# USB___mega8.net
KiCad netlist of a schematic drawn in Altium Designer
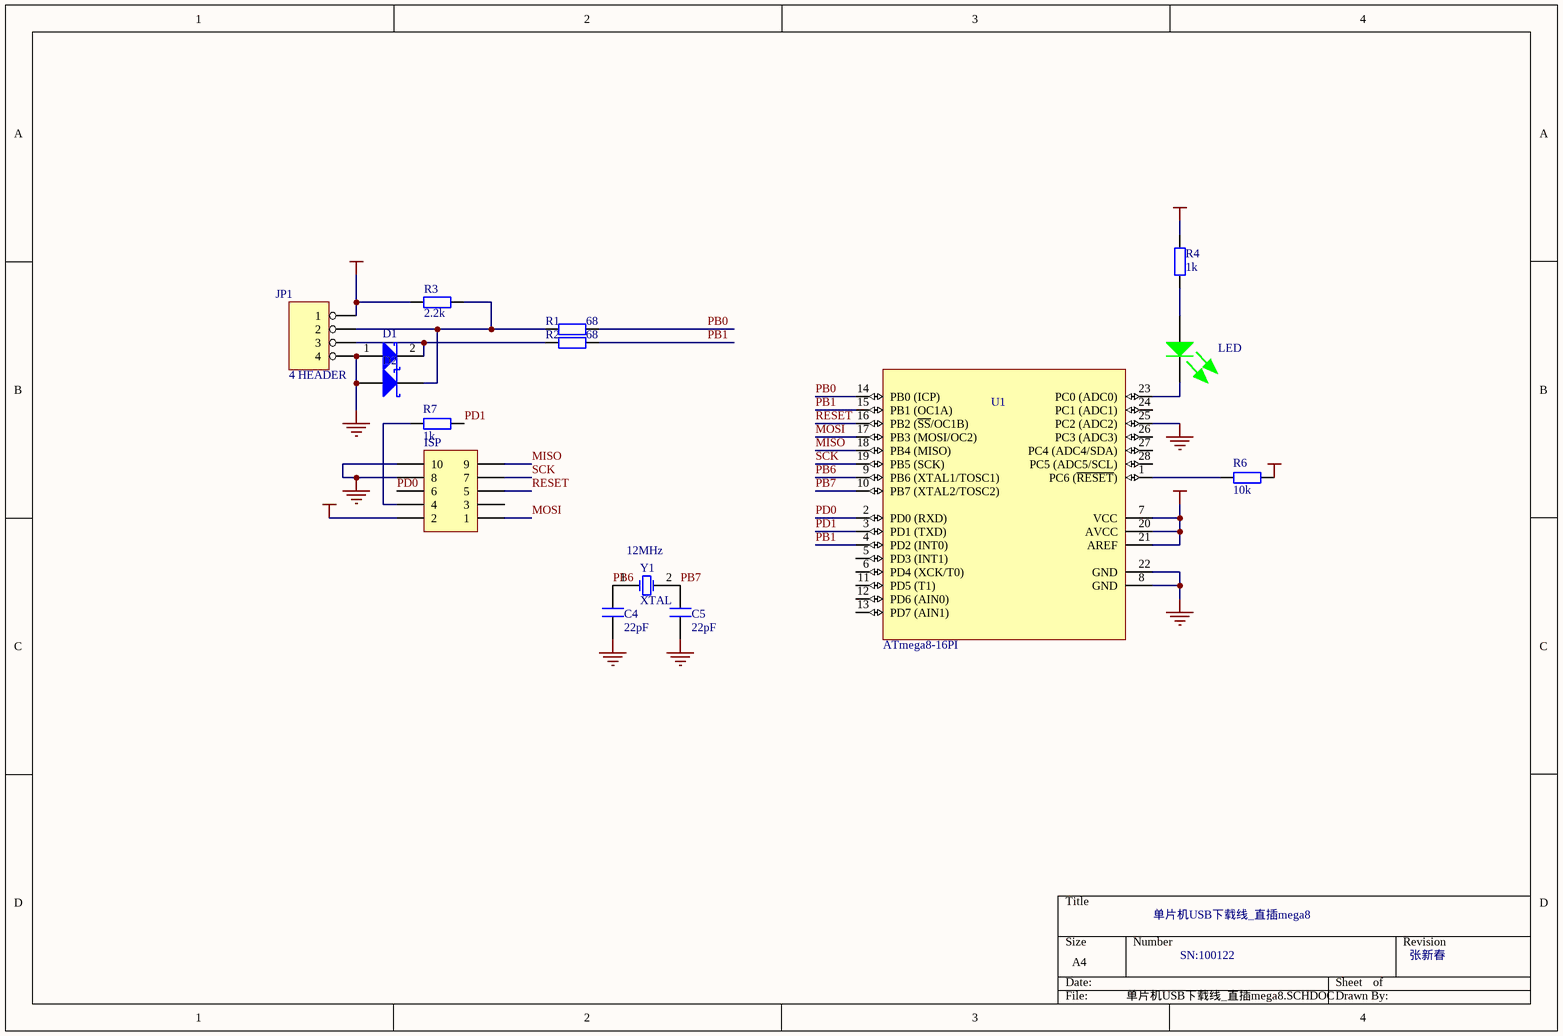
[diagram p0: 单片机USB下载线_直插mega8.SCHDOC]

(export (version "E")
  (design (tool "Eeschema 10.0.6"))
  (components
    (comp (ref "C4")
      (value "22pF")
      (footprint "TP-0805-R")
      (description "Capacitor SMD1206")
      (libsource (lib "*") (part "CAPSMD"))
    )
    (comp (ref "C5")
      (value "22pF")
      (footprint "TP-0805-R")
      (description "Capacitor SMD1206")
      (libsource (lib "*") (part "CAPSMD"))
    )
    (comp (ref "D1")
      (value "Diode 11DQ03")
      (footprint "TPDR")
      (description "Schottky Rectifier")
      (fields (field (name "PUBLISHER") "Altium Limited"))
      (libsource (lib "Miscellaneous Devices") (part "Diode 11DQ03"))
    )
    (comp (ref "D2")
      (value "Diode 11DQ03")
      (footprint "TPDR")
      (description "Schottky Rectifier")
      (fields (field (name "PUBLISHER") "Altium Limited"))
      (libsource (lib "") (part "Diode 11DQ03_1"))
    )
    (comp (ref "ISP")
      (value "~")
      (footprint "HDR2X5")
      (description "Header, 5-Pin, Dual row, Right Angle")
      (fields (field (name "MANUFACTURER") "Generic Components"))
      (libsource (lib "*") (part "MLW10A"))
    )
    (comp (ref "JP1")
      (value "4 HEADER")
      (footprint "USB-5V")
      (description "4 Pin Header")
      (libsource (lib "*") (part "4 HEADER"))
    )
    (comp (ref "LED")
      (value "~")
      (footprint "TP-0805-D")
      (description "Zöld Led 3mm")
      (libsource (lib "*") (part "LED Zöld"))
    )
    (comp (ref "R1")
      (value "68")
      (footprint "TP-0805-R")
      (description "Resistor SMD1206, 1% fémréteg")
      (libsource (lib "*") (part "RES"))
    )
    (comp (ref "R2")
      (value "68")
      (footprint "TP-0805-R")
      (description "Resistor SMD1206, 1% fémréteg")
      (libsource (lib "*") (part "RES"))
    )
    (comp (ref "R3")
      (value "2.2k")
      (footprint "TP-0805-R")
      (description "Resistor SMD1206, 1% fémréteg")
      (libsource (lib "*") (part "RES"))
    )
    (comp (ref "R4")
      (value "1k")
      (footprint "TP-0805-R")
      (description "Resistor SMD1206, 1% fémréteg")
      (libsource (lib "*") (part "RES"))
    )
    (comp (ref "R6")
      (value "10k")
      (footprint "TP-0805-R")
      (description "Resistor SMD1206, 1% fémréteg")
      (libsource (lib "*") (part "RES"))
    )
    (comp (ref "R7")
      (value "1k")
      (footprint "TP-0805-R")
      (description "Resistor SMD1206, 1% fémréteg")
      (libsource (lib "*") (part "RES"))
    )
    (comp (ref "U1")
      (value "ATmega8-16PI")
      (footprint "28P3")
      (description "8-Bit AVR Microcontroller with 8K Bytes of In-System Programmable Flash Memory")
      (fields (field (name "PUBLISHER") "Altium Limited"))
      (libsource (lib "Atmel Microcontroller 8-Bit AVR") (part "ATmega8-16PI"))
    )
    (comp (ref "Y1")
      (value "XTAL")
      (footprint "JZ_ZC")
      (description "Crystal Oscillator")
      (fields
        (field (name "MANUFACTURER") "Generic Components")
        (field (name "ALTIUM_VALUE") "12MHz")
        (field (name "PUBLISHER") "Altium Hobart Technology Centre")
      )
      (libsource (lib "*") (part "XTAL"))
    )
  )
  (nets
    (net (code "1") (name "/MISO") (class "Default")
      (node (ref "ISP") (pin "9") (pinfunction "9_9") (pintype "passive"))
      (node (ref "U1") (pin "18") (pinfunction "PB4_(MISO)_18") (pintype "bidirectional"))
    )
    (net (code "2") (name "/MOSI") (class "Default")
      (node (ref "ISP") (pin "1") (pinfunction "1_1") (pintype "passive"))
      (node (ref "U1") (pin "17") (pinfunction "PB3_(MOSI/OC2)_17") (pintype "bidirectional"))
    )
    (net (code "3") (name "/PB0") (class "Default")
      (node (ref "R1") (pin "2") (pinfunction "2_2") (pintype "passive"))
      (node (ref "U1") (pin "14") (pinfunction "PB0_(ICP)_14") (pintype "bidirectional"))
    )
    (net (code "4") (name "/PB1") (class "Default")
      (node (ref "R2") (pin "1") (pinfunction "1_1") (pintype "passive"))
      (node (ref "U1") (pin "15") (pinfunction "PB1_(OC1A)_15") (pintype "bidirectional"))
      (node (ref "U1") (pin "4") (pinfunction "PD2_(INT0)_4") (pintype "bidirectional"))
    )
    (net (code "5") (name "/PB6") (class "Default")
      (node (ref "C4") (pin "2") (pinfunction "2_2") (pintype "passive"))
      (node (ref "U1") (pin "9") (pinfunction "PB6_(XTAL1/TOSC1)_9") (pintype "bidirectional"))
      (node (ref "Y1") (pin "1") (pinfunction "OSC1_1") (pintype "passive"))
    )
    (net (code "6") (name "/PB7") (class "Default")
      (node (ref "C5") (pin "2") (pinfunction "2_2") (pintype "passive"))
      (node (ref "U1") (pin "10") (pinfunction "PB7_(XTAL2/TOSC2)_10") (pintype "bidirectional"))
      (node (ref "Y1") (pin "2") (pinfunction "OSC2_2") (pintype "passive"))
    )
    (net (code "7") (name "/PD0") (class "Default")
      (node (ref "ISP") (pin "6") (pinfunction "6_6") (pintype "passive"))
      (node (ref "U1") (pin "2") (pinfunction "PD0_(RXD)_2") (pintype "bidirectional"))
    )
    (net (code "8") (name "/PD1") (class "Default")
      (node (ref "R7") (pin "2") (pinfunction "2_2") (pintype "passive"))
      (node (ref "U1") (pin "3") (pinfunction "PD1_(TXD)_3") (pintype "bidirectional"))
    )
    (net (code "9") (name "/RESET") (class "Default")
      (node (ref "ISP") (pin "5") (pinfunction "5_5") (pintype "passive"))
      (node (ref "U1") (pin "16") (pinfunction "PB2_(~{SS}/OC1B)_16") (pintype "bidirectional"))
    )
    (net (code "10") (name "/SCK") (class "Default")
      (node (ref "ISP") (pin "7") (pinfunction "7_7") (pintype "passive"))
      (node (ref "U1") (pin "19") (pinfunction "PB5_(SCK)_19") (pintype "bidirectional"))
    )
    (net (code "11") (name "GND") (class "Default")
      (node (ref "C4") (pin "1") (pinfunction "1_1") (pintype "passive"))
      (node (ref "C5") (pin "1") (pinfunction "1_1") (pintype "passive"))
      (node (ref "D1") (pin "1") (pinfunction "A_1") (pintype "passive"))
      (node (ref "D2") (pin "1") (pinfunction "A_1") (pintype "passive"))
      (node (ref "ISP") (pin "10") (pinfunction "10_10") (pintype "passive"))
      (node (ref "ISP") (pin "8") (pinfunction "8_8") (pintype "passive"))
      (node (ref "JP1") (pin "4") (pinfunction "4_4") (pintype "passive"))
      (node (ref "U1") (pin "22") (pinfunction "GND_22") (pintype "power_in"))
      (node (ref "U1") (pin "25") (pinfunction "PC2_(ADC2)_25") (pintype "bidirectional"))
      (node (ref "U1") (pin "8") (pinfunction "GND_8") (pintype "power_in"))
    )
    (net (code "12") (name "Net-(D1-K)") (class "Default")
      (node (ref "D1") (pin "2") (pinfunction "K_2") (pintype "passive"))
      (node (ref "JP1") (pin "3") (pinfunction "3_3") (pintype "passive"))
      (node (ref "R2") (pin "2") (pinfunction "2_2") (pintype "passive"))
    )
    (net (code "13") (name "Net-(D2-K)") (class "Default")
      (node (ref "D2") (pin "2") (pinfunction "K_2") (pintype "passive"))
      (node (ref "JP1") (pin "2") (pinfunction "2_2") (pintype "passive"))
      (node (ref "R1") (pin "1") (pinfunction "1_1") (pintype "passive"))
      (node (ref "R3") (pin "1") (pinfunction "1_1") (pintype "passive"))
    )
    (net (code "14") (name "Net-(ISP-Pad4)") (class "Default")
      (node (ref "ISP") (pin "4") (pinfunction "4_4") (pintype "passive"))
      (node (ref "R7") (pin "1") (pinfunction "1_1") (pintype "passive"))
    )
    (net (code "15") (name "Net-(LED-Pad1)") (class "Default")
      (node (ref "LED") (pin "1") (pinfunction "1_1") (pintype "passive"))
      (node (ref "R4") (pin "1") (pinfunction "1_1") (pintype "passive"))
    )
    (net (code "16") (name "Net-(U1-PC0_(ADC0))") (class "Default")
      (node (ref "LED") (pin "2") (pinfunction "2_2") (pintype "passive"))
      (node (ref "U1") (pin "23") (pinfunction "PC0_(ADC0)_23") (pintype "bidirectional"))
    )
    (net (code "17") (name "Net-(U1-PC6_(~{RESET}))") (class "Default")
      (node (ref "R6") (pin "1") (pinfunction "1_1") (pintype "passive"))
      (node (ref "U1") (pin "1") (pinfunction "PC6_(~{RESET})_1") (pintype "bidirectional"))
    )
    (net (code "18") (name "VCC") (class "Default")
      (node (ref "ISP") (pin "2") (pinfunction "2_2") (pintype "passive"))
      (node (ref "JP1") (pin "1") (pinfunction "1_1") (pintype "passive"))
      (node (ref "R3") (pin "2") (pinfunction "2_2") (pintype "passive"))
      (node (ref "R4") (pin "2") (pinfunction "2_2") (pintype "passive"))
      (node (ref "R6") (pin "2") (pinfunction "2_2") (pintype "passive"))
      (node (ref "U1") (pin "20") (pinfunction "AVCC_20") (pintype "power_in"))
      (node (ref "U1") (pin "21") (pinfunction "AREF_21") (pintype "passive"))
      (node (ref "U1") (pin "7") (pinfunction "VCC_7") (pintype "power_in"))
    )
    (net (code "19") (name "unconnected-(ISP-Pad3)") (class "Default")
      (node (ref "ISP") (pin "3") (pinfunction "3_3") (pintype "passive"))
    )
    (net (code "20") (name "unconnected-(U1-PC1_(ADC1)-Pad24)") (class "Default")
      (node (ref "U1") (pin "24") (pinfunction "PC1_(ADC1)_24") (pintype "bidirectional"))
    )
    (net (code "21") (name "unconnected-(U1-PC3_(ADC3)-Pad26)") (class "Default")
      (node (ref "U1") (pin "26") (pinfunction "PC3_(ADC3)_26") (pintype "bidirectional"))
    )
    (net (code "22") (name "unconnected-(U1-PC4_(ADC4{slash}SDA)-Pad27)") (class "Default")
      (node (ref "U1") (pin "27") (pinfunction "PC4_(ADC4/SDA)_27") (pintype "bidirectional"))
    )
    (net (code "23") (name "unconnected-(U1-PC5_(ADC5{slash}SCL)-Pad28)") (class "Default")
      (node (ref "U1") (pin "28") (pinfunction "PC5_(ADC5/SCL)_28") (pintype "bidirectional"))
    )
    (net (code "24") (name "unconnected-(U1-PD3_(INT1)-Pad5)") (class "Default")
      (node (ref "U1") (pin "5") (pinfunction "PD3_(INT1)_5") (pintype "bidirectional"))
    )
    (net (code "25") (name "unconnected-(U1-PD4_(XCK{slash}T0)-Pad6)") (class "Default")
      (node (ref "U1") (pin "6") (pinfunction "PD4_(XCK/T0)_6") (pintype "bidirectional"))
    )
    (net (code "26") (name "unconnected-(U1-PD5_(T1)-Pad11)") (class "Default")
      (node (ref "U1") (pin "11") (pinfunction "PD5_(T1)_11") (pintype "bidirectional"))
    )
    (net (code "27") (name "unconnected-(U1-PD6_(AIN0)-Pad12)") (class "Default")
      (node (ref "U1") (pin "12") (pinfunction "PD6_(AIN0)_12") (pintype "bidirectional"))
    )
    (net (code "28") (name "unconnected-(U1-PD7_(AIN1)-Pad13)") (class "Default")
      (node (ref "U1") (pin "13") (pinfunction "PD7_(AIN1)_13") (pintype "bidirectional"))
    )
  )
)
